# SPI_IFC.net
KiCad netlist of a schematic drawn in Altium Designer
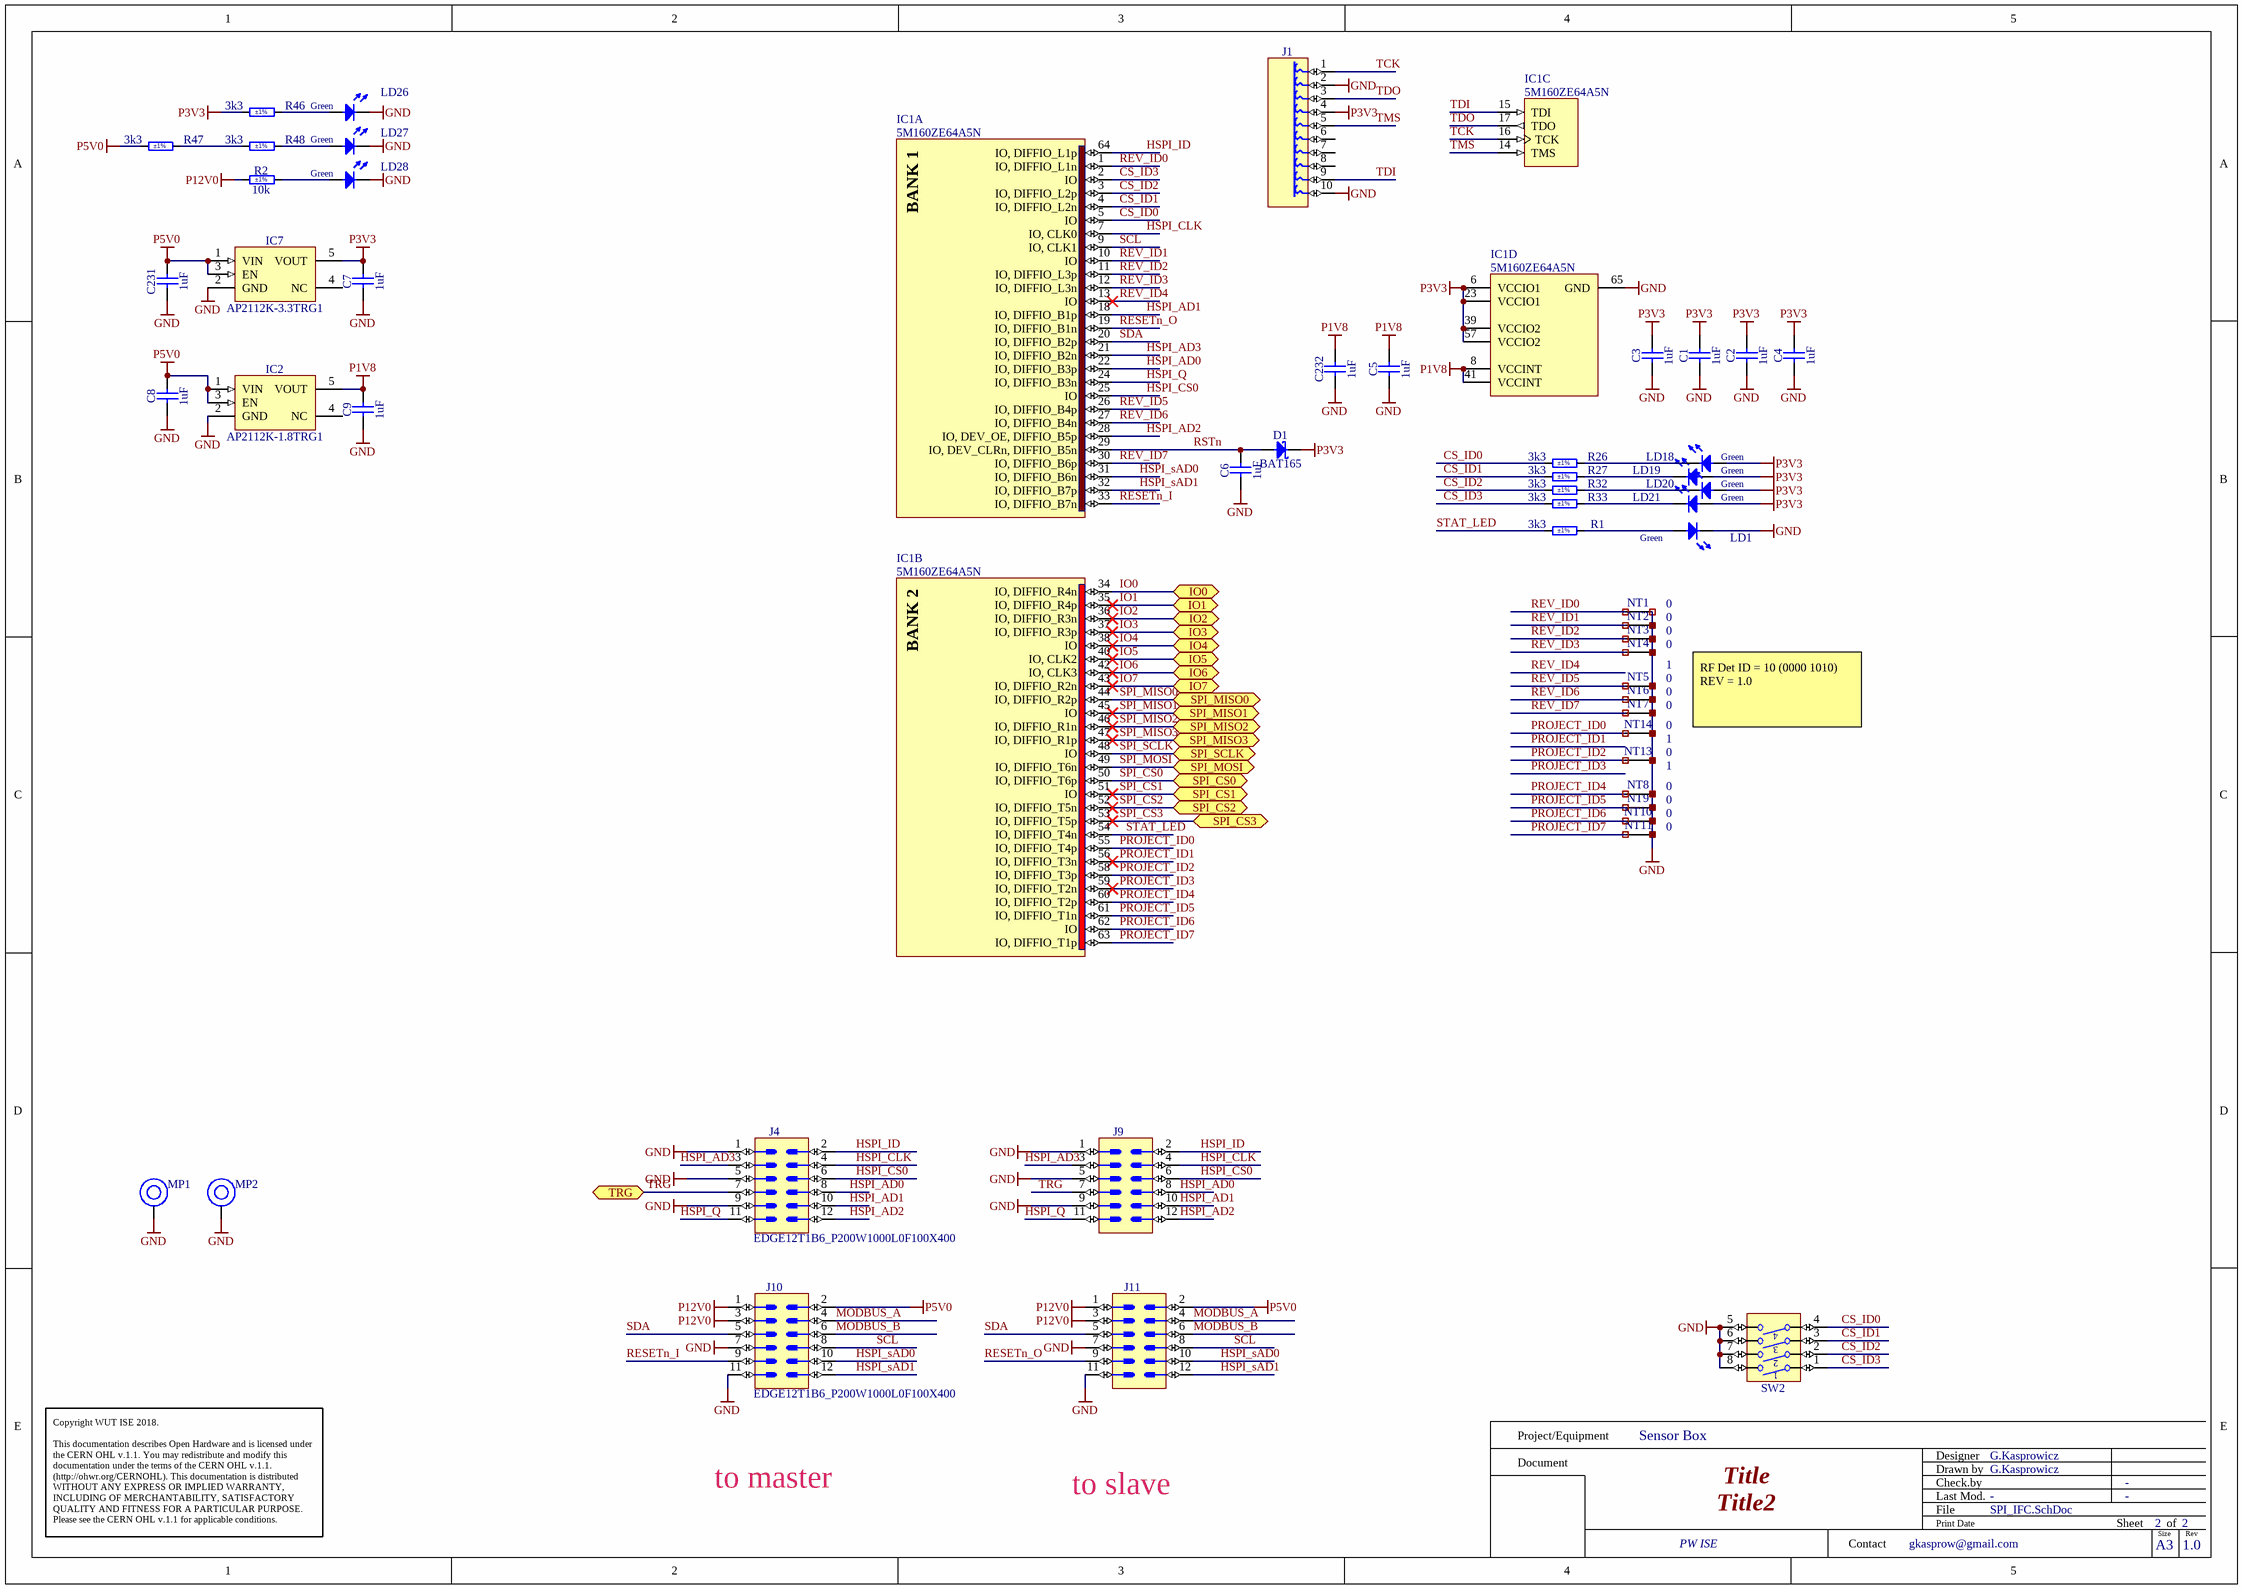
[diagram p0: SPI_IFC.SchDoc]

(export (version "E")
  (design (tool "Eeschema 10.0.6"))
  (components
    (comp (ref "C1")
      (value "1uF")
      (footprint "CAPC1005X55N")
      (description "Non-polarised capacitor")
      (fields
        (field (name "PART NUMBER") "CC0402_1UF_16V_10%_X5R")
        (field (name "VOLTAGE") "16V")
        (field (name "AUTHOR") "CERN DEM JLC")
      )
      (libsource (lib "Capacitors") (part "Capacitor - non polarized"))
    )
    (comp (ref "C2")
      (value "1uF")
      (footprint "CAPC1005X55N")
      (description "Non-polarised capacitor")
      (fields
        (field (name "PART NUMBER") "CC0402_1UF_16V_10%_X5R")
        (field (name "VOLTAGE") "16V")
        (field (name "AUTHOR") "CERN DEM JLC")
      )
      (libsource (lib "Capacitors") (part "Capacitor - non polarized"))
    )
    (comp (ref "C3")
      (value "1uF")
      (footprint "CAPC1005X55N")
      (description "Non-polarised capacitor")
      (fields
        (field (name "PART NUMBER") "CC0402_1UF_16V_10%_X5R")
        (field (name "VOLTAGE") "16V")
        (field (name "AUTHOR") "CERN DEM JLC")
      )
      (libsource (lib "Capacitors") (part "Capacitor - non polarized"))
    )
    (comp (ref "C4")
      (value "1uF")
      (footprint "CAPC1005X55N")
      (description "Non-polarised capacitor")
      (fields
        (field (name "PART NUMBER") "CC0402_1UF_16V_10%_X5R")
        (field (name "VOLTAGE") "16V")
        (field (name "AUTHOR") "CERN DEM JLC")
      )
      (libsource (lib "Capacitors") (part "Capacitor - non polarized"))
    )
    (comp (ref "C5")
      (value "1uF")
      (footprint "CAPC1005X55N")
      (description "Non-polarised capacitor")
      (fields
        (field (name "PART NUMBER") "CC0402_1UF_16V_10%_X5R")
        (field (name "VOLTAGE") "16V")
        (field (name "AUTHOR") "CERN DEM JLC")
      )
      (libsource (lib "Capacitors") (part "Capacitor - non polarized"))
    )
    (comp (ref "C6")
      (value "1uF")
      (footprint "CAPC1005X55N")
      (description "Non-polarised capacitor")
      (fields
        (field (name "PART NUMBER") "CC0402_1UF_16V_10%_X5R")
        (field (name "VOLTAGE") "16V")
        (field (name "AUTHOR") "CERN DEM JLC")
      )
      (libsource (lib "Capacitors") (part "Capacitor - non polarized"))
    )
    (comp (ref "C7")
      (value "1uF")
      (footprint "CAPC1005X55N")
      (description "Non-polarised capacitor")
      (fields
        (field (name "PART NUMBER") "CC0402_1UF_16V_10%_X5R")
        (field (name "VOLTAGE") "16V")
        (field (name "AUTHOR") "CERN DEM JLC")
      )
      (libsource (lib "Capacitors") (part "Capacitor - non polarized"))
    )
    (comp (ref "C8")
      (value "1uF")
      (footprint "CAPC1005X55N")
      (description "Non-polarised capacitor")
      (fields
        (field (name "PART NUMBER") "CC0402_1UF_16V_10%_X5R")
        (field (name "VOLTAGE") "16V")
        (field (name "AUTHOR") "CERN DEM JLC")
      )
      (libsource (lib "Capacitors") (part "Capacitor - non polarized"))
    )
    (comp (ref "C9")
      (value "1uF")
      (footprint "CAPC1005X55N")
      (description "Non-polarised capacitor")
      (fields
        (field (name "PART NUMBER") "CC0402_1UF_16V_10%_X5R")
        (field (name "VOLTAGE") "16V")
        (field (name "AUTHOR") "CERN DEM JLC")
      )
      (libsource (lib "Capacitors") (part "Capacitor - non polarized"))
    )
    (comp (ref "C231")
      (value "1uF")
      (footprint "CAPC1005X55N")
      (description "Non-polarised capacitor")
      (fields
        (field (name "PART NUMBER") "CC0402_1UF_16V_10%_X5R")
        (field (name "VOLTAGE") "16V")
        (field (name "AUTHOR") "CERN DEM JLC")
      )
      (libsource (lib "Capacitors") (part "Capacitor - non polarized"))
    )
    (comp (ref "C232")
      (value "1uF")
      (footprint "CAPC1005X55N")
      (description "Non-polarised capacitor")
      (fields
        (field (name "PART NUMBER") "CC0402_1UF_16V_10%_X5R")
        (field (name "VOLTAGE") "16V")
        (field (name "AUTHOR") "CERN DEM JLC")
      )
      (libsource (lib "Capacitors") (part "Capacitor - non polarized"))
    )
    (comp (ref "D1")
      (value "BAT165")
      (footprint "SOD2512X110N")
      (description "Schottky Diode")
      (fields
        (field (name "VOLTAGE") "40V")
        (field (name "POWER") "750mA")
        (field (name "AUTHOR") "CERN DEM JLC")
      )
      (libsource (lib "ICs And Semiconductors") (part "Diode Schottky"))
    )
    (comp (ref "IC1")
      (value "5M160ZE64A5N")
      (footprint "QFP40P900X900X120-65N-S550")
      (fields (field (name "MANUFACTURER") "ALTERA") (field (name "AUTHOR") "CERN DEM JLC"))
      (libsource (lib "ICs And Semiconductors") (part "5M160ZE64A5N"))
    )
    (comp (ref "IC2")
      (value "AP2112K-1.8TRG1")
      (footprint "SOT95P285X140-5N")
      (description "600mA CMOS Low Dropout Linear Regulator with Enable")
      (fields
        (field (name "MANUFACTURER") "DIODES INCORPORATED")
        (field (name "MANUFACTURER PART NUMBER") "AP2112K-1.8")
        (field (name "AUTHOR") "CERN DEM JLC")
      )
      (libsource (lib "ICs And Semiconductors") (part "AP2112K"))
    )
    (comp (ref "IC7")
      (value "AP2112K-3.3TRG1")
      (footprint "SOT95P285X140-5N")
      (description "600mA CMOS Low Dropout Linear Regulator with Enable")
      (fields
        (field (name "MANUFACTURER") "DIODES INCORPORATED")
        (field (name "MANUFACTURER PART NUMBER") "AP2112K-3.3")
        (field (name "AUTHOR") "CERN DEM MR")
      )
      (libsource (lib "ICs And Semiconductors") (part "AP2112K"))
    )
    (comp (ref "J1")
      (value "TC2050-IDC")
      (footprint "TC2050-IDC")
      (description "TC2030-MCP and TC2050-IDC Pad Contact")
      (fields (field (name "AUTHOR") "CERN DEM HF"))
      (libsource (lib "Eletro-mechanical") (part "TC2050-IDC"))
    )
    (comp (ref "J4")
      (value "~")
      (footprint "EDGE12T1B6_P200W1000L0F100X400")
      (description "PCB Edge Connector 12 (2x6)")
      (fields
        (field (name "PART NUMBER") "EDGE10T1B6_P200W1000L0F100X400")
        (field (name "AUTHOR") "CERN DEM MR")
      )
      (libsource (lib "Connectors") (part "PCB Edge Connector 12 (2x6)"))
    )
    (comp (ref "J9")
      (value "~")
      (footprint "EDGE12T5B10_P200W1000L0F100X400")
      (description "PCB Edge Connector 12 (2x6)")
      (fields (field (name "PART NUMBER") "EDGE12T5B10_P200W1000L0F100X400") (field (name "AUTHOR") "GK"))
      (libsource (lib "Connectors") (part "PCB Edge Connector 12 (2x6) R"))
    )
    (comp (ref "J10")
      (value "~")
      (footprint "EDGE12T1B6_P200W1000L0F100X400")
      (description "PCB Edge Connector 12 (2x6)")
      (fields
        (field (name "PART NUMBER") "EDGE10T1B6_P200W1000L0F100X400")
        (field (name "AUTHOR") "CERN DEM MR")
      )
      (libsource (lib "Connectors") (part "PCB Edge Connector 12 (2x6)"))
    )
    (comp (ref "J11")
      (value "~")
      (footprint "EDGE12T5B10_P200W1000L0F100X400")
      (description "PCB Edge Connector 12 (2x6)")
      (fields (field (name "PART NUMBER") "EDGE12T5B10_P200W1000L0F100X400") (field (name "AUTHOR") "GK"))
      (libsource (lib "Connectors") (part "PCB Edge Connector 12 (2x6) R"))
    )
    (comp (ref "LD1")
      (value "Green")
      (footprint "LED_KINGBRIGHT_KP-1608CGCK")
      (description "LED Green 1C 2A")
      (fields
        (field (name "PART NUMBER") "LED_KINGBRIGHT_KP-1608CGCK")
        (field (name "MANUFACTURER") "KINGBRIGHT")
        (field (name "AUTHOR") "CERN DEM HF")
      )
      (libsource (lib "ICs And Semiconductors") (part "LED Green 1C 2A"))
    )
    (comp (ref "LD18")
      (value "Green")
      (footprint "LED_KINGBRIGHT_KP-1608CGCK")
      (description "LED Green 1C 2A")
      (fields
        (field (name "PART NUMBER") "LED_KINGBRIGHT_KP-1608CGCK")
        (field (name "MANUFACTURER") "KINGBRIGHT")
        (field (name "AUTHOR") "CERN DEM HF")
      )
      (libsource (lib "ICs And Semiconductors") (part "LED Green 1C 2A"))
    )
    (comp (ref "LD19")
      (value "Green")
      (footprint "LED_KINGBRIGHT_KP-1608CGCK")
      (description "LED Green 1C 2A")
      (fields
        (field (name "PART NUMBER") "LED_KINGBRIGHT_KP-1608CGCK")
        (field (name "MANUFACTURER") "KINGBRIGHT")
        (field (name "AUTHOR") "CERN DEM HF")
      )
      (libsource (lib "ICs And Semiconductors") (part "LED Green 1C 2A"))
    )
    (comp (ref "LD20")
      (value "Green")
      (footprint "LED_KINGBRIGHT_KP-1608CGCK")
      (description "LED Green 1C 2A")
      (fields
        (field (name "PART NUMBER") "LED_KINGBRIGHT_KP-1608CGCK")
        (field (name "MANUFACTURER") "KINGBRIGHT")
        (field (name "AUTHOR") "CERN DEM HF")
      )
      (libsource (lib "ICs And Semiconductors") (part "LED Green 1C 2A"))
    )
    (comp (ref "LD21")
      (value "Green")
      (footprint "LED_KINGBRIGHT_KP-1608CGCK")
      (description "LED Green 1C 2A")
      (fields
        (field (name "PART NUMBER") "LED_KINGBRIGHT_KP-1608CGCK")
        (field (name "MANUFACTURER") "KINGBRIGHT")
        (field (name "AUTHOR") "CERN DEM HF")
      )
      (libsource (lib "ICs And Semiconductors") (part "LED Green 1C 2A"))
    )
    (comp (ref "LD26")
      (value "Green")
      (footprint "LED_KINGBRIGHT_KP-1608CGCK")
      (description "LED Green 1C 2A")
      (fields
        (field (name "PART NUMBER") "LED_KINGBRIGHT_KP-1608CGCK")
        (field (name "MANUFACTURER") "KINGBRIGHT")
        (field (name "AUTHOR") "CERN DEM HF")
      )
      (libsource (lib "ICs And Semiconductors") (part "LED Green 1C 2A"))
    )
    (comp (ref "LD27")
      (value "Green")
      (footprint "LED_KINGBRIGHT_KP-1608CGCK")
      (description "LED Green 1C 2A")
      (fields
        (field (name "PART NUMBER") "LED_KINGBRIGHT_KP-1608CGCK")
        (field (name "MANUFACTURER") "KINGBRIGHT")
        (field (name "AUTHOR") "CERN DEM HF")
      )
      (libsource (lib "ICs And Semiconductors") (part "LED Green 1C 2A"))
    )
    (comp (ref "LD28")
      (value "Green")
      (footprint "LED_KINGBRIGHT_KP-1608CGCK")
      (description "LED Green 1C 2A")
      (fields
        (field (name "PART NUMBER") "LED_KINGBRIGHT_KP-1608CGCK")
        (field (name "MANUFACTURER") "KINGBRIGHT")
        (field (name "AUTHOR") "CERN DEM HF")
      )
      (libsource (lib "ICs And Semiconductors") (part "LED Green 1C 2A"))
    )
    (comp (ref "MP1")
      (value "M1.6 x 3mm")
      (footprint "97730306330")
      (description "WA-SMSI SMT Steel Spacer with internal Thread Bottom closed, OD 3.3mm, M1.6 x 3mm")
      (fields
        (field (name "MANUFACTURER PART NUMBER") "97730306330R")
        (field (name "MANUFACTURER") "Wurth Elektronik")
      )
      (libsource (lib "Altium_WA-SMSI (rev22a)") (part "97730306330R"))
    )
    (comp (ref "MP2")
      (value "M1.6 x 3mm")
      (footprint "97730306330")
      (description "WA-SMSI SMT Steel Spacer with internal Thread Bottom closed, OD 3.3mm, M1.6 x 3mm")
      (fields
        (field (name "MANUFACTURER PART NUMBER") "97730306330R")
        (field (name "MANUFACTURER") "Wurth Elektronik")
      )
      (libsource (lib "Altium_WA-SMSI (rev22a)") (part "97730306330R"))
    )
    (comp (ref "NT1")
      (value "Net Tie")
      (footprint "Net Tie 3")
      (fields (field (name "PART NUMBER") "Net Tie 3") (field (name "AUTHOR") "CERN DEM HF"))
      (libsource (lib "Eletro-mechanical") (part "Net Tie_a"))
    )
    (comp (ref "NT2")
      (value "Net Tie")
      (footprint "Net Tie 3")
      (fields (field (name "PART NUMBER") "Net Tie 3") (field (name "AUTHOR") "CERN DEM HF"))
      (libsource (lib "Eletro-mechanical") (part "Net Tie_a"))
    )
    (comp (ref "NT3")
      (value "Net Tie")
      (footprint "Net Tie 3")
      (fields (field (name "PART NUMBER") "Net Tie 3") (field (name "AUTHOR") "CERN DEM HF"))
      (libsource (lib "Eletro-mechanical") (part "Net Tie_a"))
    )
    (comp (ref "NT4")
      (value "Net Tie")
      (footprint "Net Tie 3")
      (fields (field (name "PART NUMBER") "Net Tie 3") (field (name "AUTHOR") "CERN DEM HF"))
      (libsource (lib "Eletro-mechanical") (part "Net Tie_a"))
    )
    (comp (ref "NT5")
      (value "Net Tie")
      (footprint "Net Tie 3")
      (fields (field (name "PART NUMBER") "Net Tie 3") (field (name "AUTHOR") "CERN DEM HF"))
      (libsource (lib "Eletro-mechanical") (part "Net Tie_a"))
    )
    (comp (ref "NT6")
      (value "Net Tie")
      (footprint "Net Tie 3")
      (fields (field (name "PART NUMBER") "Net Tie 3") (field (name "AUTHOR") "CERN DEM HF"))
      (libsource (lib "Eletro-mechanical") (part "Net Tie_a"))
    )
    (comp (ref "NT7")
      (value "Net Tie")
      (footprint "Net Tie 3")
      (fields (field (name "PART NUMBER") "Net Tie 3") (field (name "AUTHOR") "CERN DEM HF"))
      (libsource (lib "Eletro-mechanical") (part "Net Tie_a"))
    )
    (comp (ref "NT8")
      (value "Net Tie")
      (footprint "Net Tie 3")
      (fields (field (name "PART NUMBER") "Net Tie 3") (field (name "AUTHOR") "CERN DEM HF"))
      (libsource (lib "Eletro-mechanical") (part "Net Tie_a"))
    )
    (comp (ref "NT9")
      (value "Net Tie")
      (footprint "Net Tie 3")
      (fields (field (name "PART NUMBER") "Net Tie 3") (field (name "AUTHOR") "CERN DEM HF"))
      (libsource (lib "Eletro-mechanical") (part "Net Tie_a"))
    )
    (comp (ref "NT10")
      (value "Net Tie")
      (footprint "Net Tie 3")
      (fields (field (name "PART NUMBER") "Net Tie 3") (field (name "AUTHOR") "CERN DEM HF"))
      (libsource (lib "Eletro-mechanical") (part "Net Tie_a"))
    )
    (comp (ref "NT11")
      (value "Net Tie")
      (footprint "Net Tie 3")
      (fields (field (name "PART NUMBER") "Net Tie 3") (field (name "AUTHOR") "CERN DEM HF"))
      (libsource (lib "Eletro-mechanical") (part "Net Tie_a"))
    )
    (comp (ref "NT13")
      (value "Net Tie")
      (footprint "Net Tie 3")
      (fields (field (name "PART NUMBER") "Net Tie 3") (field (name "AUTHOR") "CERN DEM HF"))
      (libsource (lib "Eletro-mechanical") (part "Net Tie_a"))
    )
    (comp (ref "NT14")
      (value "Net Tie")
      (footprint "Net Tie 3")
      (fields (field (name "PART NUMBER") "Net Tie 3") (field (name "AUTHOR") "CERN DEM HF"))
      (libsource (lib "Eletro-mechanical") (part "Net Tie_a"))
    )
    (comp (ref "R1")
      (value "3k3")
      (footprint "RESC1005X40N")
      (description "Resistor - 1%")
      (fields
        (field (name "TOLERANCE") "±1%")
        (field (name "PART NUMBER") "R0402_3K3_1%_0.0625W_100PPM")
        (field (name "POWER") "0.0625W")
        (field (name "AUTHOR") "CERN DEM JLC")
      )
      (libsource (lib "Resistors") (part "Resistor - 1%"))
    )
    (comp (ref "R2")
      (value "10k")
      (footprint "RESC1005X40N")
      (description "Resistor - 1%")
      (fields
        (field (name "TOLERANCE") "±1%")
        (field (name "PART NUMBER") "R0402_10K_1%_0.0625W_100PPM")
        (field (name "POWER") "0.0625W")
        (field (name "AUTHOR") "CERN DEM JLC")
      )
      (libsource (lib "Resistors") (part "Resistor - 1%"))
    )
    (comp (ref "R26")
      (value "3k3")
      (footprint "RESC1005X40N")
      (description "Resistor - 1%")
      (fields
        (field (name "TOLERANCE") "±1%")
        (field (name "PART NUMBER") "R0402_3K3_1%_0.0625W_100PPM")
        (field (name "POWER") "0.0625W")
        (field (name "AUTHOR") "CERN DEM JLC")
      )
      (libsource (lib "Resistors") (part "Resistor - 1%"))
    )
    (comp (ref "R27")
      (value "3k3")
      (footprint "RESC1005X40N")
      (description "Resistor - 1%")
      (fields
        (field (name "TOLERANCE") "±1%")
        (field (name "PART NUMBER") "R0402_3K3_1%_0.0625W_100PPM")
        (field (name "POWER") "0.0625W")
        (field (name "AUTHOR") "CERN DEM JLC")
      )
      (libsource (lib "Resistors") (part "Resistor - 1%"))
    )
    (comp (ref "R32")
      (value "3k3")
      (footprint "RESC1005X40N")
      (description "Resistor - 1%")
      (fields
        (field (name "TOLERANCE") "±1%")
        (field (name "PART NUMBER") "R0402_3K3_1%_0.0625W_100PPM")
        (field (name "POWER") "0.0625W")
        (field (name "AUTHOR") "CERN DEM JLC")
      )
      (libsource (lib "Resistors") (part "Resistor - 1%"))
    )
    (comp (ref "R33")
      (value "3k3")
      (footprint "RESC1005X40N")
      (description "Resistor - 1%")
      (fields
        (field (name "TOLERANCE") "±1%")
        (field (name "PART NUMBER") "R0402_3K3_1%_0.0625W_100PPM")
        (field (name "POWER") "0.0625W")
        (field (name "AUTHOR") "CERN DEM JLC")
      )
      (libsource (lib "Resistors") (part "Resistor - 1%"))
    )
    (comp (ref "R46")
      (value "3k3")
      (footprint "RESC1005X40N")
      (description "Resistor - 1%")
      (fields
        (field (name "TOLERANCE") "±1%")
        (field (name "PART NUMBER") "R0402_3K3_1%_0.0625W_100PPM")
        (field (name "POWER") "0.0625W")
        (field (name "AUTHOR") "CERN DEM JLC")
      )
      (libsource (lib "Resistors") (part "Resistor - 1%"))
    )
    (comp (ref "R47")
      (value "3k3")
      (footprint "RESC1005X40N")
      (description "Resistor - 1%")
      (fields
        (field (name "TOLERANCE") "±1%")
        (field (name "PART NUMBER") "R0402_3K3_1%_0.0625W_100PPM")
        (field (name "POWER") "0.0625W")
        (field (name "AUTHOR") "CERN DEM JLC")
      )
      (libsource (lib "Resistors") (part "Resistor - 1%"))
    )
    (comp (ref "R48")
      (value "3k3")
      (footprint "RESC1005X40N")
      (description "Resistor - 1%")
      (fields
        (field (name "TOLERANCE") "±1%")
        (field (name "PART NUMBER") "R0402_3K3_1%_0.0625W_100PPM")
        (field (name "POWER") "0.0625W")
        (field (name "AUTHOR") "CERN DEM JLC")
      )
      (libsource (lib "Resistors") (part "Resistor - 1%"))
    )
    (comp (ref "SW2")
      (value "Switch")
      (footprint "SW_OMRON_A6H-4102")
      (description "4 Ways SPST DIP Switch")
      (fields
        (field (name "PART NUMBER") "SW_OMRON_A6H-4102")
        (field (name "MANUFACTURER") "OMRON")
        (field (name "AUTHOR") "CERN DEM JLC")
      )
      (libsource (lib "Eletro-mechanical") (part "SW 4x SPST DIP Switch"))
    )
  )
  (nets
    (net (code "1") (name "/CS_ID0") (class "Default")
      (node (ref "IC1") (pin "5") (pinfunction "IO_5") (pintype "bidirectional"))
      (node (ref "R26") (pin "2") (pinfunction "2_2") (pintype "passive"))
      (node (ref "SW2") (pin "4") (pinfunction "4_4") (pintype "bidirectional"))
    )
    (net (code "2") (name "/CS_ID1") (class "Default")
      (node (ref "IC1") (pin "4") (pinfunction "IO,_DIFFIO_L2n_4") (pintype "bidirectional"))
      (node (ref "R27") (pin "2") (pinfunction "2_2") (pintype "passive"))
      (node (ref "SW2") (pin "3") (pinfunction "3_3") (pintype "bidirectional"))
    )
    (net (code "3") (name "/CS_ID2") (class "Default")
      (node (ref "IC1") (pin "3") (pinfunction "IO,_DIFFIO_L2p_3") (pintype "bidirectional"))
      (node (ref "R32") (pin "2") (pinfunction "2_2") (pintype "passive"))
      (node (ref "SW2") (pin "2") (pinfunction "2_2") (pintype "bidirectional"))
    )
    (net (code "4") (name "/CS_ID3") (class "Default")
      (node (ref "IC1") (pin "2") (pinfunction "IO_2") (pintype "bidirectional"))
      (node (ref "R33") (pin "2") (pinfunction "2_2") (pintype "passive"))
      (node (ref "SW2") (pin "1") (pinfunction "1_1") (pintype "bidirectional"))
    )
    (net (code "5") (name "/HSPI_AD0") (class "Default")
      (node (ref "IC1") (pin "22") (pinfunction "IO,_DIFFIO_B3p_22") (pintype "bidirectional"))
      (node (ref "J4") (pin "8") (pinfunction "8_8") (pintype "bidirectional"))
      (node (ref "J9") (pin "8") (pinfunction "8_8") (pintype "bidirectional"))
    )
    (net (code "6") (name "/HSPI_AD1") (class "Default")
      (node (ref "IC1") (pin "18") (pinfunction "IO,_DIFFIO_B1p_18") (pintype "bidirectional"))
      (node (ref "J4") (pin "10") (pinfunction "10_10") (pintype "bidirectional"))
      (node (ref "J9") (pin "10") (pinfunction "10_10") (pintype "bidirectional"))
    )
    (net (code "7") (name "/HSPI_AD2") (class "Default")
      (node (ref "IC1") (pin "28") (pinfunction "IO,_DEV_OE,_DIFFIO_B5p_28") (pintype "bidirectional"))
      (node (ref "J4") (pin "12") (pinfunction "12_12") (pintype "bidirectional"))
      (node (ref "J9") (pin "12") (pinfunction "12_12") (pintype "bidirectional"))
    )
    (net (code "8") (name "/HSPI_AD3") (class "Default")
      (node (ref "IC1") (pin "21") (pinfunction "IO,_DIFFIO_B2n_21") (pintype "bidirectional"))
      (node (ref "J4") (pin "3") (pinfunction "3_3") (pintype "bidirectional"))
      (node (ref "J9") (pin "3") (pinfunction "3_3") (pintype "bidirectional"))
    )
    (net (code "9") (name "/HSPI_CLK") (class "Default")
      (node (ref "IC1") (pin "7") (pinfunction "IO,_CLK0_7") (pintype "bidirectional"))
      (node (ref "J4") (pin "4") (pinfunction "4_4") (pintype "bidirectional"))
      (node (ref "J9") (pin "4") (pinfunction "4_4") (pintype "bidirectional"))
    )
    (net (code "10") (name "/HSPI_CS0") (class "Default")
      (node (ref "IC1") (pin "25") (pinfunction "IO_25") (pintype "bidirectional"))
      (node (ref "J4") (pin "6") (pinfunction "6_6") (pintype "bidirectional"))
      (node (ref "J9") (pin "6") (pinfunction "6_6") (pintype "bidirectional"))
    )
    (net (code "11") (name "/HSPI_ID") (class "Default")
      (node (ref "IC1") (pin "64") (pinfunction "IO,_DIFFIO_L1p_64") (pintype "bidirectional"))
      (node (ref "J4") (pin "2") (pinfunction "2_2") (pintype "bidirectional"))
      (node (ref "J9") (pin "2") (pinfunction "2_2") (pintype "bidirectional"))
    )
    (net (code "12") (name "/HSPI_Q") (class "Default")
      (node (ref "IC1") (pin "24") (pinfunction "IO,_DIFFIO_B3n_24") (pintype "bidirectional"))
      (node (ref "J4") (pin "11") (pinfunction "11_11") (pintype "bidirectional"))
      (node (ref "J9") (pin "11") (pinfunction "11_11") (pintype "bidirectional"))
    )
    (net (code "13") (name "/HSPI_sAD0") (class "Default")
      (node (ref "IC1") (pin "31") (pinfunction "IO,_DIFFIO_B6n_31") (pintype "bidirectional"))
      (node (ref "J10") (pin "10") (pinfunction "10_10") (pintype "bidirectional"))
      (node (ref "J11") (pin "10") (pinfunction "10_10") (pintype "bidirectional"))
    )
    (net (code "14") (name "/HSPI_sAD1") (class "Default")
      (node (ref "IC1") (pin "32") (pinfunction "IO,_DIFFIO_B7p_32") (pintype "bidirectional"))
      (node (ref "J10") (pin "12") (pinfunction "12_12") (pintype "bidirectional"))
      (node (ref "J11") (pin "12") (pinfunction "12_12") (pintype "bidirectional"))
    )
    (net (code "15") (name "/IO0") (class "Default")
      (node (ref "IC1") (pin "34") (pinfunction "IO,_DIFFIO_R4n_34") (pintype "bidirectional"))
    )
    (net (code "16") (name "/IO1") (class "Default")
      (node (ref "IC1") (pin "35") (pinfunction "IO,_DIFFIO_R4p_35") (pintype "bidirectional+no_connect"))
    )
    (net (code "17") (name "/IO2") (class "Default")
      (node (ref "IC1") (pin "36") (pinfunction "IO,_DIFFIO_R3n_36") (pintype "bidirectional+no_connect"))
    )
    (net (code "18") (name "/IO3") (class "Default")
      (node (ref "IC1") (pin "37") (pinfunction "IO,_DIFFIO_R3p_37") (pintype "bidirectional+no_connect"))
    )
    (net (code "19") (name "/IO4") (class "Default")
      (node (ref "IC1") (pin "38") (pinfunction "IO_38") (pintype "bidirectional+no_connect"))
    )
    (net (code "20") (name "/IO5") (class "Default")
      (node (ref "IC1") (pin "40") (pinfunction "IO,_CLK2_40") (pintype "bidirectional+no_connect"))
    )
    (net (code "21") (name "/IO6") (class "Default")
      (node (ref "IC1") (pin "42") (pinfunction "IO,_CLK3_42") (pintype "bidirectional+no_connect"))
    )
    (net (code "22") (name "/IO7") (class "Default")
      (node (ref "IC1") (pin "43") (pinfunction "IO,_DIFFIO_R2n_43") (pintype "bidirectional+no_connect"))
    )
    (net (code "23") (name "/MODBUS_A") (class "Default")
      (node (ref "J10") (pin "4") (pinfunction "4_4") (pintype "bidirectional"))
      (node (ref "J11") (pin "4") (pinfunction "4_4") (pintype "bidirectional"))
    )
    (net (code "24") (name "/MODBUS_B") (class "Default")
      (node (ref "J10") (pin "6") (pinfunction "6_6") (pintype "bidirectional"))
      (node (ref "J11") (pin "6") (pinfunction "6_6") (pintype "bidirectional"))
    )
    (net (code "25") (name "/PROJECT_ID0") (class "Default")
      (node (ref "IC1") (pin "55") (pinfunction "IO,_DIFFIO_T4p_55") (pintype "bidirectional"))
      (node (ref "NT14") (pin "1") (pinfunction "1_1") (pintype "bidirectional"))
    )
    (net (code "26") (name "/PROJECT_ID1") (class "Default")
      (node (ref "IC1") (pin "56") (pinfunction "IO,_DIFFIO_T3n_56") (pintype "bidirectional"))
    )
    (net (code "27") (name "/PROJECT_ID2") (class "Default")
      (node (ref "IC1") (pin "58") (pinfunction "IO,_DIFFIO_T3p_58") (pintype "bidirectional"))
      (node (ref "NT13") (pin "1") (pinfunction "1_1") (pintype "bidirectional"))
    )
    (net (code "28") (name "/PROJECT_ID3") (class "Default")
      (node (ref "IC1") (pin "59") (pinfunction "IO,_DIFFIO_T2n_59") (pintype "bidirectional"))
    )
    (net (code "29") (name "/PROJECT_ID4") (class "Default")
      (node (ref "IC1") (pin "60") (pinfunction "IO,_DIFFIO_T2p_60") (pintype "bidirectional"))
      (node (ref "NT8") (pin "1") (pinfunction "1_1") (pintype "bidirectional"))
    )
    (net (code "30") (name "/PROJECT_ID5") (class "Default")
      (node (ref "IC1") (pin "61") (pinfunction "IO,_DIFFIO_T1n_61") (pintype "bidirectional"))
      (node (ref "NT9") (pin "1") (pinfunction "1_1") (pintype "bidirectional"))
    )
    (net (code "31") (name "/PROJECT_ID6") (class "Default")
      (node (ref "IC1") (pin "62") (pinfunction "IO_62") (pintype "bidirectional"))
      (node (ref "NT10") (pin "1") (pinfunction "1_1") (pintype "bidirectional"))
    )
    (net (code "32") (name "/PROJECT_ID7") (class "Default")
      (node (ref "IC1") (pin "63") (pinfunction "IO,_DIFFIO_T1p_63") (pintype "bidirectional"))
      (node (ref "NT11") (pin "1") (pinfunction "1_1") (pintype "bidirectional"))
    )
    (net (code "33") (name "/RESETn_I") (class "Default")
      (node (ref "IC1") (pin "33") (pinfunction "IO,_DIFFIO_B7n_33") (pintype "bidirectional"))
      (node (ref "J10") (pin "9") (pinfunction "9_9") (pintype "bidirectional"))
    )
    (net (code "34") (name "/RESETn_O") (class "Default")
      (node (ref "IC1") (pin "19") (pinfunction "IO,_DIFFIO_B1n_19") (pintype "bidirectional"))
      (node (ref "J11") (pin "9") (pinfunction "9_9") (pintype "bidirectional"))
    )
    (net (code "35") (name "/REV_ID0") (class "Default")
      (node (ref "IC1") (pin "1") (pinfunction "IO,_DIFFIO_L1n_1") (pintype "bidirectional"))
      (node (ref "NT1") (pin "1") (pinfunction "1_1") (pintype "bidirectional"))
    )
    (net (code "36") (name "/REV_ID1") (class "Default")
      (node (ref "IC1") (pin "10") (pinfunction "IO_10") (pintype "bidirectional"))
      (node (ref "NT2") (pin "1") (pinfunction "1_1") (pintype "bidirectional"))
    )
    (net (code "37") (name "/REV_ID2") (class "Default")
      (node (ref "IC1") (pin "11") (pinfunction "IO,_DIFFIO_L3p_11") (pintype "bidirectional"))
      (node (ref "NT3") (pin "1") (pinfunction "1_1") (pintype "bidirectional"))
    )
    (net (code "38") (name "/REV_ID3") (class "Default")
      (node (ref "IC1") (pin "12") (pinfunction "IO,_DIFFIO_L3n_12") (pintype "bidirectional"))
      (node (ref "NT4") (pin "1") (pinfunction "1_1") (pintype "bidirectional"))
    )
    (net (code "39") (name "/REV_ID4") (class "Default")
      (node (ref "IC1") (pin "13") (pinfunction "IO_13") (pintype "bidirectional"))
    )
    (net (code "40") (name "/REV_ID5") (class "Default")
      (node (ref "IC1") (pin "26") (pinfunction "IO,_DIFFIO_B4p_26") (pintype "bidirectional"))
      (node (ref "NT5") (pin "1") (pinfunction "1_1") (pintype "bidirectional"))
    )
    (net (code "41") (name "/REV_ID6") (class "Default")
      (node (ref "IC1") (pin "27") (pinfunction "IO,_DIFFIO_B4n_27") (pintype "bidirectional"))
      (node (ref "NT6") (pin "1") (pinfunction "1_1") (pintype "bidirectional"))
    )
    (net (code "42") (name "/REV_ID7") (class "Default")
      (node (ref "IC1") (pin "30") (pinfunction "IO,_DIFFIO_B6p_30") (pintype "bidirectional"))
      (node (ref "NT7") (pin "1") (pinfunction "1_1") (pintype "bidirectional"))
    )
    (net (code "43") (name "/RSTn") (class "Default")
      (node (ref "C6") (pin "2") (pinfunction "2_2") (pintype "passive"))
      (node (ref "D1") (pin "2") (pinfunction "A_2") (pintype "passive"))
      (node (ref "IC1") (pin "29") (pinfunction "IO,_DEV_CLRn,_DIFFIO_B5n_29") (pintype "bidirectional"))
    )
    (net (code "44") (name "/SCL") (class "Default")
      (node (ref "IC1") (pin "9") (pinfunction "IO,_CLK1_9") (pintype "bidirectional"))
      (node (ref "J10") (pin "8") (pinfunction "8_8") (pintype "bidirectional"))
      (node (ref "J11") (pin "8") (pinfunction "8_8") (pintype "bidirectional"))
    )
    (net (code "45") (name "/SDA") (class "Default")
      (node (ref "IC1") (pin "20") (pinfunction "IO,_DIFFIO_B2p_20") (pintype "bidirectional"))
      (node (ref "J10") (pin "5") (pinfunction "5_5") (pintype "bidirectional"))
      (node (ref "J11") (pin "5") (pinfunction "5_5") (pintype "bidirectional"))
    )
    (net (code "46") (name "/SPI_CS0") (class "Default")
      (node (ref "IC1") (pin "50") (pinfunction "IO,_DIFFIO_T6p_50") (pintype "bidirectional"))
    )
    (net (code "47") (name "/SPI_CS1") (class "Default")
      (node (ref "IC1") (pin "51") (pinfunction "IO_51") (pintype "bidirectional+no_connect"))
    )
    (net (code "48") (name "/SPI_CS2") (class "Default")
      (node (ref "IC1") (pin "52") (pinfunction "IO,_DIFFIO_T5n_52") (pintype "bidirectional+no_connect"))
    )
    (net (code "49") (name "/SPI_CS3") (class "Default")
      (node (ref "IC1") (pin "53") (pinfunction "IO,_DIFFIO_T5p_53") (pintype "bidirectional+no_connect"))
    )
    (net (code "50") (name "/SPI_MISO0") (class "Default")
      (node (ref "IC1") (pin "44") (pinfunction "IO,_DIFFIO_R2p_44") (pintype "bidirectional"))
    )
    (net (code "51") (name "/SPI_MISO1") (class "Default")
      (node (ref "IC1") (pin "45") (pinfunction "IO_45") (pintype "bidirectional+no_connect"))
    )
    (net (code "52") (name "/SPI_MISO2") (class "Default")
      (node (ref "IC1") (pin "46") (pinfunction "IO,_DIFFIO_R1n_46") (pintype "bidirectional+no_connect"))
    )
    (net (code "53") (name "/SPI_MISO3") (class "Default")
      (node (ref "IC1") (pin "47") (pinfunction "IO,_DIFFIO_R1p_47") (pintype "bidirectional+no_connect"))
    )
    (net (code "54") (name "/SPI_MOSI") (class "Default")
      (node (ref "IC1") (pin "49") (pinfunction "IO,_DIFFIO_T6n_49") (pintype "bidirectional"))
    )
    (net (code "55") (name "/SPI_SCLK") (class "Default")
      (node (ref "IC1") (pin "48") (pinfunction "IO_48") (pintype "bidirectional"))
    )
    (net (code "56") (name "/STAT_LED") (class "Default")
      (node (ref "IC1") (pin "54") (pinfunction "IO,_DIFFIO_T4n_54") (pintype "bidirectional"))
      (node (ref "R1") (pin "2") (pinfunction "2_2") (pintype "passive"))
    )
    (net (code "57") (name "/TCK") (class "Default")
      (node (ref "IC1") (pin "16") (pinfunction "TCK_16") (pintype "input"))
      (node (ref "J1") (pin "1") (pinfunction "1_1") (pintype "bidirectional"))
    )
    (net (code "58") (name "/TDI") (class "Default")
      (node (ref "IC1") (pin "15") (pinfunction "TDI_15") (pintype "input"))
      (node (ref "J1") (pin "9") (pinfunction "9_9") (pintype "bidirectional"))
    )
    (net (code "59") (name "/TDO") (class "Default")
      (node (ref "IC1") (pin "17") (pinfunction "TDO_17") (pintype "output"))
      (node (ref "J1") (pin "3") (pinfunction "3_3") (pintype "bidirectional"))
    )
    (net (code "60") (name "/TMS") (class "Default")
      (node (ref "IC1") (pin "14") (pinfunction "TMS_14") (pintype "input"))
      (node (ref "J1") (pin "5") (pinfunction "5_5") (pintype "bidirectional"))
    )
    (net (code "61") (name "/TRG") (class "Default")
      (node (ref "J4") (pin "7") (pinfunction "7_7") (pintype "bidirectional"))
      (node (ref "J9") (pin "7") (pinfunction "7_7") (pintype "bidirectional"))
    )
    (net (code "62") (name "GND") (class "Default")
      (node (ref "C1") (pin "1") (pinfunction "1_1") (pintype "passive"))
      (node (ref "C2") (pin "1") (pinfunction "1_1") (pintype "passive"))
      (node (ref "C231") (pin "1") (pinfunction "1_1") (pintype "passive"))
      (node (ref "C232") (pin "1") (pinfunction "1_1") (pintype "passive"))
      (node (ref "C3") (pin "1") (pinfunction "1_1") (pintype "passive"))
      (node (ref "C4") (pin "1") (pinfunction "1_1") (pintype "passive"))
      (node (ref "C5") (pin "1") (pinfunction "1_1") (pintype "passive"))
      (node (ref "C6") (pin "1") (pinfunction "1_1") (pintype "passive"))
      (node (ref "C7") (pin "1") (pinfunction "1_1") (pintype "passive"))
      (node (ref "C8") (pin "1") (pinfunction "1_1") (pintype "passive"))
      (node (ref "C9") (pin "1") (pinfunction "1_1") (pintype "passive"))
      (node (ref "IC1") (pin "65") (pinfunction "GND_65") (pintype "power_in"))
      (node (ref "IC2") (pin "2") (pinfunction "GND_2") (pintype "power_in"))
      (node (ref "IC7") (pin "2") (pinfunction "GND_2") (pintype "power_in"))
      (node (ref "J1") (pin "10") (pinfunction "10_10") (pintype "bidirectional"))
      (node (ref "J1") (pin "2") (pinfunction "2_2") (pintype "bidirectional"))
      (node (ref "J10") (pin "11") (pinfunction "11_11") (pintype "bidirectional"))
      (node (ref "J10") (pin "7") (pinfunction "7_7") (pintype "bidirectional"))
      (node (ref "J11") (pin "11") (pinfunction "11_11") (pintype "bidirectional"))
      (node (ref "J11") (pin "7") (pinfunction "7_7") (pintype "bidirectional"))
      (node (ref "J4") (pin "1") (pinfunction "1_1") (pintype "bidirectional"))
      (node (ref "J4") (pin "5") (pinfunction "5_5") (pintype "bidirectional"))
      (node (ref "J4") (pin "9") (pinfunction "9_9") (pintype "bidirectional"))
      (node (ref "J9") (pin "1") (pinfunction "1_1") (pintype "bidirectional"))
      (node (ref "J9") (pin "5") (pinfunction "5_5") (pintype "bidirectional"))
      (node (ref "J9") (pin "9") (pinfunction "9_9") (pintype "bidirectional"))
      (node (ref "LD1") (pin "1") (pinfunction "C_1") (pintype "passive"))
      (node (ref "LD26") (pin "1") (pinfunction "C_1") (pintype "passive"))
      (node (ref "LD27") (pin "1") (pinfunction "C_1") (pintype "passive"))
      (node (ref "LD28") (pin "1") (pinfunction "C_1") (pintype "passive"))
      (node (ref "MP1") (pin "1") (pinfunction "1_1") (pintype "passive"))
      (node (ref "MP2") (pin "1") (pinfunction "1_1") (pintype "passive"))
      (node (ref "NT1") (pin "2") (pinfunction "2_2") (pintype "bidirectional"))
      (node (ref "NT10") (pin "2") (pinfunction "2_2") (pintype "bidirectional"))
      (node (ref "NT11") (pin "2") (pinfunction "2_2") (pintype "bidirectional"))
      (node (ref "NT13") (pin "2") (pinfunction "2_2") (pintype "bidirectional"))
      (node (ref "NT14") (pin "2") (pinfunction "2_2") (pintype "bidirectional"))
      (node (ref "NT2") (pin "2") (pinfunction "2_2") (pintype "bidirectional"))
      (node (ref "NT3") (pin "2") (pinfunction "2_2") (pintype "bidirectional"))
      (node (ref "NT4") (pin "2") (pinfunction "2_2") (pintype "bidirectional"))
      (node (ref "NT5") (pin "2") (pinfunction "2_2") (pintype "bidirectional"))
      (node (ref "NT6") (pin "2") (pinfunction "2_2") (pintype "bidirectional"))
      (node (ref "NT7") (pin "2") (pinfunction "2_2") (pintype "bidirectional"))
      (node (ref "NT8") (pin "2") (pinfunction "2_2") (pintype "bidirectional"))
      (node (ref "NT9") (pin "2") (pinfunction "2_2") (pintype "bidirectional"))
      (node (ref "SW2") (pin "5") (pinfunction "5_5") (pintype "bidirectional"))
      (node (ref "SW2") (pin "6") (pinfunction "6_6") (pintype "bidirectional"))
      (node (ref "SW2") (pin "7") (pinfunction "7_7") (pintype "bidirectional"))
      (node (ref "SW2") (pin "8") (pinfunction "8_8") (pintype "bidirectional"))
    )
    (net (code "63") (name "Net-(LD1-A)") (class "Default")
      (node (ref "LD1") (pin "2") (pinfunction "A_2") (pintype "passive"))
      (node (ref "R1") (pin "1") (pinfunction "1_1") (pintype "passive"))
    )
    (net (code "64") (name "Net-(LD18-C)") (class "Default")
      (node (ref "LD18") (pin "1") (pinfunction "C_1") (pintype "passive"))
      (node (ref "R26") (pin "1") (pinfunction "1_1") (pintype "passive"))
    )
    (net (code "65") (name "Net-(LD19-C)") (class "Default")
      (node (ref "LD19") (pin "1") (pinfunction "C_1") (pintype "passive"))
      (node (ref "R27") (pin "1") (pinfunction "1_1") (pintype "passive"))
    )
    (net (code "66") (name "Net-(LD20-C)") (class "Default")
      (node (ref "LD20") (pin "1") (pinfunction "C_1") (pintype "passive"))
      (node (ref "R32") (pin "1") (pinfunction "1_1") (pintype "passive"))
    )
    (net (code "67") (name "Net-(LD21-C)") (class "Default")
      (node (ref "LD21") (pin "1") (pinfunction "C_1") (pintype "passive"))
      (node (ref "R33") (pin "1") (pinfunction "1_1") (pintype "passive"))
    )
    (net (code "68") (name "Net-(LD26-A)") (class "Default")
      (node (ref "LD26") (pin "2") (pinfunction "A_2") (pintype "passive"))
      (node (ref "R46") (pin "1") (pinfunction "1_1") (pintype "passive"))
    )
    (net (code "69") (name "Net-(LD27-A)") (class "Default")
      (node (ref "LD27") (pin "2") (pinfunction "A_2") (pintype "passive"))
      (node (ref "R48") (pin "1") (pinfunction "1_1") (pintype "passive"))
    )
    (net (code "70") (name "Net-(LD28-A)") (class "Default")
      (node (ref "LD28") (pin "2") (pinfunction "A_2") (pintype "passive"))
      (node (ref "R2") (pin "2") (pinfunction "2_2") (pintype "passive"))
    )
    (net (code "71") (name "Net-(R47-Pad1)") (class "Default")
      (node (ref "R47") (pin "1") (pinfunction "1_1") (pintype "passive"))
      (node (ref "R48") (pin "2") (pinfunction "2_2") (pintype "passive"))
    )
    (net (code "72") (name "P1V8") (class "Default")
      (node (ref "C232") (pin "2") (pinfunction "2_2") (pintype "passive"))
      (node (ref "C5") (pin "2") (pinfunction "2_2") (pintype "passive"))
      (node (ref "C9") (pin "2") (pinfunction "2_2") (pintype "passive"))
      (node (ref "IC1") (pin "41") (pinfunction "VCCINT_41") (pintype "power_in"))
      (node (ref "IC1") (pin "8") (pinfunction "VCCINT_8") (pintype "power_in"))
      (node (ref "IC2") (pin "5") (pinfunction "VOUT_5") (pintype "power_in"))
    )
    (net (code "73") (name "P3V3") (class "Default")
      (node (ref "C1") (pin "2") (pinfunction "2_2") (pintype "passive"))
      (node (ref "C2") (pin "2") (pinfunction "2_2") (pintype "passive"))
      (node (ref "C3") (pin "2") (pinfunction "2_2") (pintype "passive"))
      (node (ref "C4") (pin "2") (pinfunction "2_2") (pintype "passive"))
      (node (ref "C7") (pin "2") (pinfunction "2_2") (pintype "passive"))
      (node (ref "D1") (pin "1") (pinfunction "C_1") (pintype "passive"))
      (node (ref "IC1") (pin "23") (pinfunction "VCCIO1_23") (pintype "power_in"))
      (node (ref "IC1") (pin "39") (pinfunction "VCCIO2_39") (pintype "power_in"))
      (node (ref "IC1") (pin "57") (pinfunction "VCCIO2_57") (pintype "power_in"))
      (node (ref "IC1") (pin "6") (pinfunction "VCCIO1_6") (pintype "power_in"))
      (node (ref "IC7") (pin "5") (pinfunction "VOUT_5") (pintype "power_in"))
      (node (ref "J1") (pin "4") (pinfunction "4_4") (pintype "bidirectional"))
      (node (ref "LD18") (pin "2") (pinfunction "A_2") (pintype "passive"))
      (node (ref "LD19") (pin "2") (pinfunction "A_2") (pintype "passive"))
      (node (ref "LD20") (pin "2") (pinfunction "A_2") (pintype "passive"))
      (node (ref "LD21") (pin "2") (pinfunction "A_2") (pintype "passive"))
      (node (ref "R46") (pin "2") (pinfunction "2_2") (pintype "passive"))
    )
    (net (code "74") (name "P5V0") (class "Default")
      (node (ref "C231") (pin "2") (pinfunction "2_2") (pintype "passive"))
      (node (ref "C8") (pin "2") (pinfunction "2_2") (pintype "passive"))
      (node (ref "IC2") (pin "1") (pinfunction "VIN_1") (pintype "input"))
      (node (ref "IC2") (pin "3") (pinfunction "EN_3") (pintype "input"))
      (node (ref "IC7") (pin "1") (pinfunction "VIN_1") (pintype "input"))
      (node (ref "IC7") (pin "3") (pinfunction "EN_3") (pintype "input"))
      (node (ref "J10") (pin "2") (pinfunction "2_2") (pintype "bidirectional"))
      (node (ref "J11") (pin "2") (pinfunction "2_2") (pintype "bidirectional"))
      (node (ref "R47") (pin "2") (pinfunction "2_2") (pintype "passive"))
    )
    (net (code "75") (name "P12V0") (class "Default")
      (node (ref "J10") (pin "1") (pinfunction "1_1") (pintype "bidirectional"))
      (node (ref "J10") (pin "3") (pinfunction "3_3") (pintype "bidirectional"))
      (node (ref "J11") (pin "1") (pinfunction "1_1") (pintype "bidirectional"))
      (node (ref "J11") (pin "3") (pinfunction "3_3") (pintype "bidirectional"))
      (node (ref "R2") (pin "1") (pinfunction "1_1") (pintype "passive"))
    )
    (net (code "76") (name "unconnected-(IC2-NC-Pad4)") (class "Default")
      (node (ref "IC2") (pin "4") (pinfunction "NC_4") (pintype "passive"))
    )
    (net (code "77") (name "unconnected-(IC7-NC-Pad4)") (class "Default")
      (node (ref "IC7") (pin "4") (pinfunction "NC_4") (pintype "passive"))
    )
    (net (code "78") (name "unconnected-(J1-Pad6)") (class "Default")
      (node (ref "J1") (pin "6") (pinfunction "6_6") (pintype "bidirectional"))
    )
    (net (code "79") (name "unconnected-(J1-Pad7)") (class "Default")
      (node (ref "J1") (pin "7") (pinfunction "7_7") (pintype "bidirectional"))
    )
    (net (code "80") (name "unconnected-(J1-Pad8)") (class "Default")
      (node (ref "J1") (pin "8") (pinfunction "8_8") (pintype "bidirectional"))
    )
  )
)
